# 2_INTERFACES_EXTERNAS.net
KiCad netlist of a schematic drawn in Altium Designer
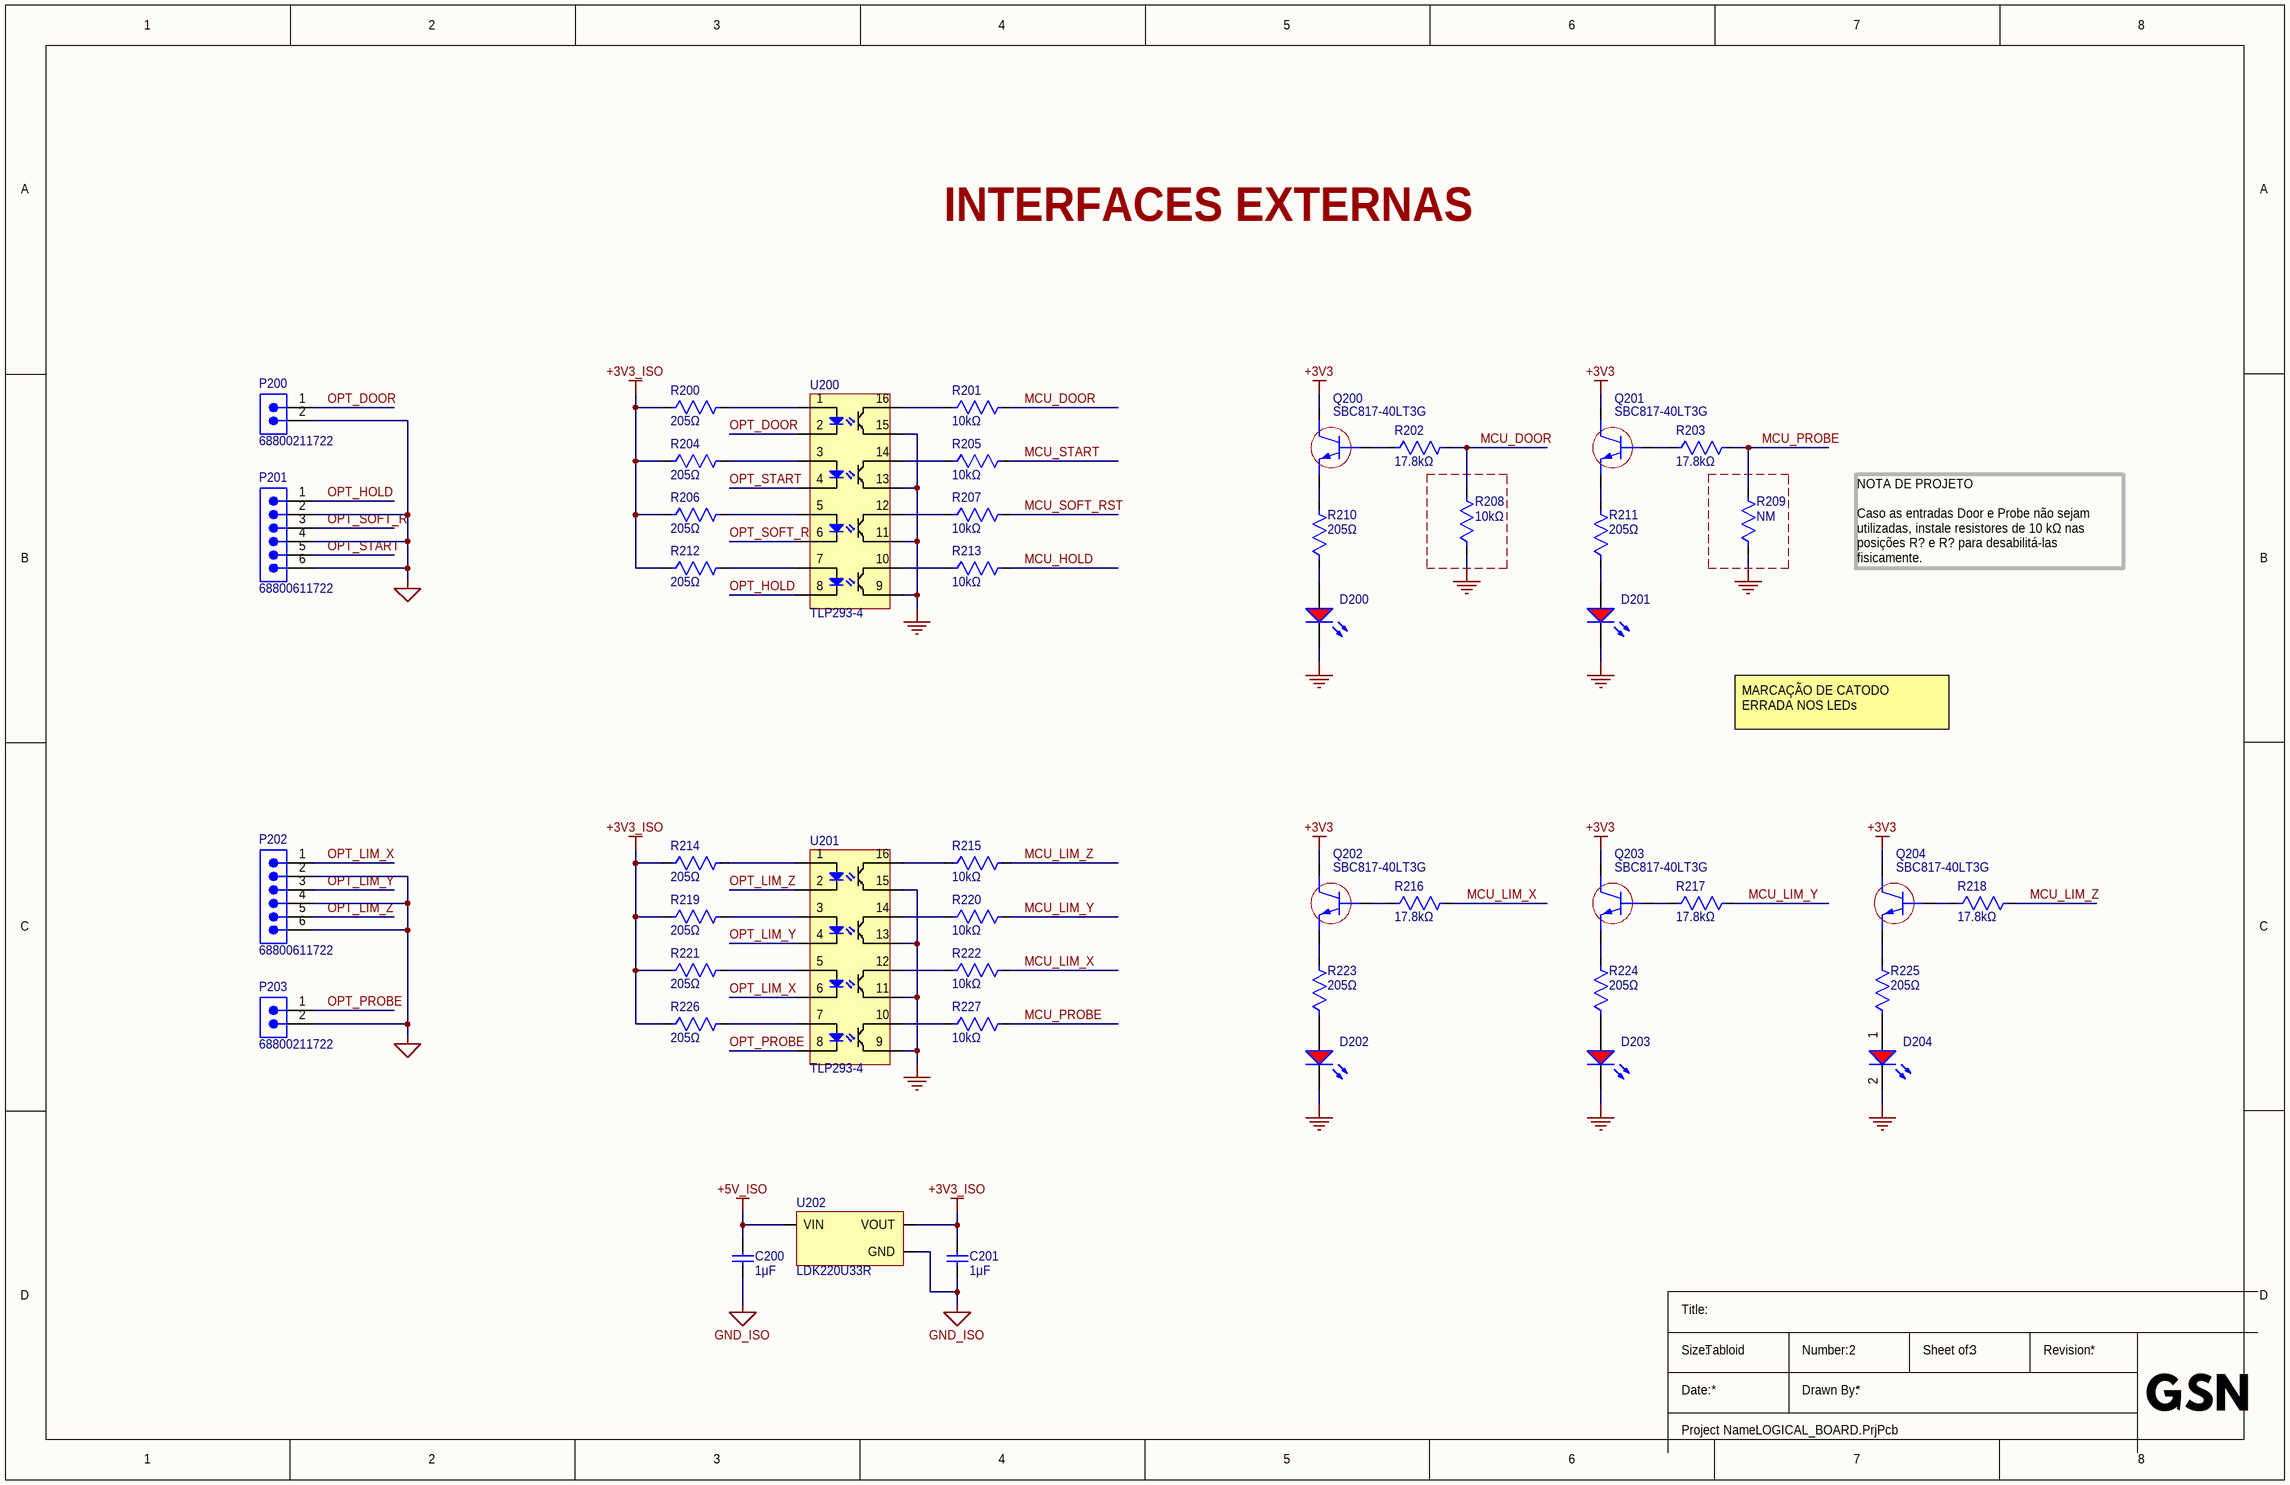
[diagram p0: 2_INTERFACES_EXTERNAS.SchDoc]

(export (version "E")
  (design (tool "Eeschema 10.0.6"))
  (components
    (comp (ref "C200")
      (value "1μF")
      (footprint "WCAP-CSGP_0603_L1.6W0.8H0.8_Wave")
      (description "WCAP-CSGP Multilayer Ceramic Chip Capacitor, General Purpose, size 0603, 1μF, 16V")
      (fields
        (field (name "MANUFACTURER PART NUMBER") "885012206052")
        (field (name "MANUFACTURER") "Wurth Elektronik")
      )
      (libsource (lib "WE - Passive Components") (part "Capacitor_Non-Polarized"))
    )
    (comp (ref "C201")
      (value "1μF")
      (footprint "WCAP-CSGP_0603_L1.6W0.8H0.8_Wave")
      (description "WCAP-CSGP Multilayer Ceramic Chip Capacitor, General Purpose, size 0603, 1μF, 16V")
      (fields
        (field (name "MANUFACTURER PART NUMBER") "885012206052")
        (field (name "MANUFACTURER") "Wurth Elektronik")
      )
      (libsource (lib "WE - Passive Components") (part "Capacitor_Non-Polarized"))
    )
    (comp (ref "D200")
      (value "Red, 2V, 140deg")
      (footprint "WL-SMCW_0603_150060xx75003")
      (description "WL-SMCW Mono-color Chip LED Waterclear, SMT, size 0603, Red, 2V, 140°")
      (fields
        (field (name "MANUFACTURER PART NUMBER") "150060RS75003")
        (field (name "MANUFACTURER") "Wurth Elektronik")
      )
      (libsource (lib "WE - Optoelectronic Components") (part "LED_Red_1A-2K"))
    )
    (comp (ref "D201")
      (value "Red, 2V, 140deg")
      (footprint "WL-SMCW_0603_150060xx75003")
      (description "WL-SMCW Mono-color Chip LED Waterclear, SMT, size 0603, Red, 2V, 140°")
      (fields
        (field (name "MANUFACTURER PART NUMBER") "150060RS75003")
        (field (name "MANUFACTURER") "Wurth Elektronik")
      )
      (libsource (lib "WE - Optoelectronic Components") (part "LED_Red_1A-2K"))
    )
    (comp (ref "D202")
      (value "Red, 2V, 140deg")
      (footprint "WL-SMCW_0603_150060xx75003")
      (description "WL-SMCW Mono-color Chip LED Waterclear, SMT, size 0603, Red, 2V, 140°")
      (fields
        (field (name "MANUFACTURER PART NUMBER") "150060RS75003")
        (field (name "MANUFACTURER") "Wurth Elektronik")
      )
      (libsource (lib "WE - Optoelectronic Components") (part "LED_Red_1A-2K"))
    )
    (comp (ref "D203")
      (value "Red, 2V, 140deg")
      (footprint "WL-SMCW_0603_150060xx75003")
      (description "WL-SMCW Mono-color Chip LED Waterclear, SMT, size 0603, Red, 2V, 140°")
      (fields
        (field (name "MANUFACTURER PART NUMBER") "150060RS75003")
        (field (name "MANUFACTURER") "Wurth Elektronik")
      )
      (libsource (lib "WE - Optoelectronic Components") (part "LED_Red_1A-2K"))
    )
    (comp (ref "D204")
      (value "Red, 2V, 140deg")
      (footprint "WL-SMCW_0603_150060xx75003")
      (description "WL-SMCW Mono-color Chip LED Waterclear, SMT, size 0603, Red, 2V, 140°")
      (fields
        (field (name "MANUFACTURER PART NUMBER") "150060RS75003")
        (field (name "MANUFACTURER") "Wurth Elektronik")
      )
      (libsource (lib "") (part "LED_Red_1A-2K_1"))
    )
    (comp (ref "P200")
      (value "68800211722")
      (footprint "68800211722")
      (description "WR-WTB “J” Type THT Male Horizontal Shrouded Header, pitch 2.5 mm, 2 pins")
      (fields (field (name "MANUFACTURER") "Wurth Elektronik"))
      (libsource (lib "WE - Electromechanical Components") (part "Header_Male_1R_02P"))
    )
    (comp (ref "P201")
      (value "68800611722")
      (footprint "68800611722")
      (description "WR-WTB “J” Type THT Male Horizontal Shrouded Header, pitch 2.5 mm, 6 pins")
      (fields (field (name "MANUFACTURER") "Wurth Elektronik"))
      (libsource (lib "WE - Electromechanical Components") (part "Header_Male_1R_06P"))
    )
    (comp (ref "P202")
      (value "68800611722")
      (footprint "68800611722")
      (description "WR-WTB “J” Type THT Male Horizontal Shrouded Header, pitch 2.5 mm, 6 pins")
      (fields (field (name "MANUFACTURER") "Wurth Elektronik"))
      (libsource (lib "WE - Electromechanical Components") (part "Header_Male_1R_06P"))
    )
    (comp (ref "P203")
      (value "68800211722")
      (footprint "68800211722")
      (description "WR-WTB “J” Type THT Male Horizontal Shrouded Header, pitch 2.5 mm, 2 pins")
      (fields (field (name "MANUFACTURER") "Wurth Elektronik"))
      (libsource (lib "WE - Electromechanical Components") (part "Header_Male_1R_02P"))
    )
    (comp (ref "Q200")
      (value "SBC817-40LT3G")
      (footprint "SOT-23-3")
      (description "TRANS NPN 45V 0.5A SOT23-3")
      (fields (field (name "MANUFACTURER") "onsemi"))
      (libsource (lib "Transistors") (part "SBC817-40LT3G"))
    )
    (comp (ref "Q201")
      (value "SBC817-40LT3G")
      (footprint "SOT-23-3")
      (description "TRANS NPN 45V 0.5A SOT23-3")
      (fields (field (name "MANUFACTURER") "onsemi"))
      (libsource (lib "Transistors") (part "SBC817-40LT3G"))
    )
    (comp (ref "Q202")
      (value "SBC817-40LT3G")
      (footprint "SOT-23-3")
      (description "TRANS NPN 45V 0.5A SOT23-3")
      (fields (field (name "MANUFACTURER") "onsemi"))
      (libsource (lib "Transistors") (part "SBC817-40LT3G"))
    )
    (comp (ref "Q203")
      (value "SBC817-40LT3G")
      (footprint "SOT-23-3")
      (description "TRANS NPN 45V 0.5A SOT23-3")
      (fields (field (name "MANUFACTURER") "onsemi"))
      (libsource (lib "Transistors") (part "SBC817-40LT3G"))
    )
    (comp (ref "Q204")
      (value "SBC817-40LT3G")
      (footprint "SOT-23-3")
      (description "TRANS NPN 45V 0.5A SOT23-3")
      (fields (field (name "MANUFACTURER") "onsemi"))
      (libsource (lib "Transistors") (part "SBC817-40LT3G"))
    )
    (comp (ref "R200")
      (value "205Ω")
      (footprint "0603-WAVE")
      (description "RES 205 OHM 1% 1/10W 0603")
      (fields
        (field (name "MANUFACTURER PART NUMBER") "RC0603FR-07205RL")
        (field (name "MANUFACTURER") "Yageo Group")
      )
      (libsource (lib "Resistors-0603-E96-Yageo") (part "RC0603FR-07205RL"))
    )
    (comp (ref "R201")
      (value "10kΩ")
      (footprint "0603-WAVE")
      (description "RES 10K OHM 1% 1/10W 0603")
      (fields
        (field (name "MANUFACTURER PART NUMBER") "RC0603FR-0710KL")
        (field (name "MANUFACTURER") "Yageo Group")
      )
      (libsource (lib "Resistors-0603-E96-Yageo") (part "RC0603FR-0710KL"))
    )
    (comp (ref "R202")
      (value "17.8kΩ")
      (footprint "0603-WAVE")
      (description "RES 17.8K OHM 1% 1/10W 0603")
      (fields
        (field (name "MANUFACTURER PART NUMBER") "RC0603FR-0717K8L")
        (field (name "MANUFACTURER") "Yageo Group")
      )
      (libsource (lib "Resistors-0603-E96-Yageo") (part "RC0603FR-0717K8L"))
    )
    (comp (ref "R203")
      (value "17.8kΩ")
      (footprint "0603-WAVE")
      (description "RES 17.8K OHM 1% 1/10W 0603")
      (fields
        (field (name "MANUFACTURER PART NUMBER") "RC0603FR-0717K8L")
        (field (name "MANUFACTURER") "Yageo Group")
      )
      (libsource (lib "Resistors-0603-E96-Yageo") (part "RC0603FR-0717K8L"))
    )
    (comp (ref "R204")
      (value "205Ω")
      (footprint "0603-WAVE")
      (description "RES 205 OHM 1% 1/10W 0603")
      (fields
        (field (name "MANUFACTURER PART NUMBER") "RC0603FR-07205RL")
        (field (name "MANUFACTURER") "Yageo Group")
      )
      (libsource (lib "Resistors-0603-E96-Yageo") (part "RC0603FR-07205RL"))
    )
    (comp (ref "R205")
      (value "10kΩ")
      (footprint "0603-WAVE")
      (description "RES 10K OHM 1% 1/10W 0603")
      (fields
        (field (name "MANUFACTURER PART NUMBER") "RC0603FR-0710KL")
        (field (name "MANUFACTURER") "Yageo Group")
      )
      (libsource (lib "Resistors-0603-E96-Yageo") (part "RC0603FR-0710KL"))
    )
    (comp (ref "R206")
      (value "205Ω")
      (footprint "0603-WAVE")
      (description "RES 205 OHM 1% 1/10W 0603")
      (fields
        (field (name "MANUFACTURER PART NUMBER") "RC0603FR-07205RL")
        (field (name "MANUFACTURER") "Yageo Group")
      )
      (libsource (lib "Resistors-0603-E96-Yageo") (part "RC0603FR-07205RL"))
    )
    (comp (ref "R207")
      (value "10kΩ")
      (footprint "0603-WAVE")
      (description "RES 10K OHM 1% 1/10W 0603")
      (fields
        (field (name "MANUFACTURER PART NUMBER") "RC0603FR-0710KL")
        (field (name "MANUFACTURER") "Yageo Group")
      )
      (libsource (lib "Resistors-0603-E96-Yageo") (part "RC0603FR-0710KL"))
    )
    (comp (ref "R208")
      (value "10kΩ")
      (footprint "0603-WAVE")
      (description "RES 10K OHM 1% 1/10W 0603")
      (fields
        (field (name "MANUFACTURER PART NUMBER") "RC0603FR-0710KL")
        (field (name "MANUFACTURER") "Yageo Group")
      )
      (libsource (lib "Resistors-0603-E96-Yageo") (part "RC0603FR-0710KL"))
    )
    (comp (ref "R209")
      (value "NM")
      (footprint "0603-WAVE")
      (description "RES 10K OHM 1% 1/10W 0603")
      (fields
        (field (name "MANUFACTURER PART NUMBER") "RC0603FR-0710KL")
        (field (name "MANUFACTURER") "Yageo Group")
      )
      (libsource (lib "Resistors-0603-E96-Yageo") (part "RC0603FR-0710KL"))
    )
    (comp (ref "R210")
      (value "205Ω")
      (footprint "0603-WAVE")
      (description "RES 205 OHM 1% 1/10W 0603")
      (fields
        (field (name "MANUFACTURER PART NUMBER") "RC0603FR-07205RL")
        (field (name "MANUFACTURER") "Yageo Group")
      )
      (libsource (lib "Resistors-0603-E96-Yageo") (part "RC0603FR-07205RL"))
    )
    (comp (ref "R211")
      (value "205Ω")
      (footprint "0603-WAVE")
      (description "RES 205 OHM 1% 1/10W 0603")
      (fields
        (field (name "MANUFACTURER PART NUMBER") "RC0603FR-07205RL")
        (field (name "MANUFACTURER") "Yageo Group")
      )
      (libsource (lib "Resistors-0603-E96-Yageo") (part "RC0603FR-07205RL"))
    )
    (comp (ref "R212")
      (value "205Ω")
      (footprint "0603-WAVE")
      (description "RES 205 OHM 1% 1/10W 0603")
      (fields
        (field (name "MANUFACTURER PART NUMBER") "RC0603FR-07205RL")
        (field (name "MANUFACTURER") "Yageo Group")
      )
      (libsource (lib "Resistors-0603-E96-Yageo") (part "RC0603FR-07205RL"))
    )
    (comp (ref "R213")
      (value "10kΩ")
      (footprint "0603-WAVE")
      (description "RES 10K OHM 1% 1/10W 0603")
      (fields
        (field (name "MANUFACTURER PART NUMBER") "RC0603FR-0710KL")
        (field (name "MANUFACTURER") "Yageo Group")
      )
      (libsource (lib "Resistors-0603-E96-Yageo") (part "RC0603FR-0710KL"))
    )
    (comp (ref "R214")
      (value "205Ω")
      (footprint "0603-WAVE")
      (description "RES 205 OHM 1% 1/10W 0603")
      (fields
        (field (name "MANUFACTURER PART NUMBER") "RC0603FR-07205RL")
        (field (name "MANUFACTURER") "Yageo Group")
      )
      (libsource (lib "Resistors-0603-E96-Yageo") (part "RC0603FR-07205RL"))
    )
    (comp (ref "R215")
      (value "10kΩ")
      (footprint "0603-WAVE")
      (description "RES 10K OHM 1% 1/10W 0603")
      (fields
        (field (name "MANUFACTURER PART NUMBER") "RC0603FR-0710KL")
        (field (name "MANUFACTURER") "Yageo Group")
      )
      (libsource (lib "Resistors-0603-E96-Yageo") (part "RC0603FR-0710KL"))
    )
    (comp (ref "R216")
      (value "17.8kΩ")
      (footprint "0603-WAVE")
      (description "RES 17.8K OHM 1% 1/10W 0603")
      (fields
        (field (name "MANUFACTURER PART NUMBER") "RC0603FR-0717K8L")
        (field (name "MANUFACTURER") "Yageo Group")
      )
      (libsource (lib "Resistors-0603-E96-Yageo") (part "RC0603FR-0717K8L"))
    )
    (comp (ref "R217")
      (value "17.8kΩ")
      (footprint "0603-WAVE")
      (description "RES 17.8K OHM 1% 1/10W 0603")
      (fields
        (field (name "MANUFACTURER PART NUMBER") "RC0603FR-0717K8L")
        (field (name "MANUFACTURER") "Yageo Group")
      )
      (libsource (lib "Resistors-0603-E96-Yageo") (part "RC0603FR-0717K8L"))
    )
    (comp (ref "R218")
      (value "17.8kΩ")
      (footprint "0603-WAVE")
      (description "RES 17.8K OHM 1% 1/10W 0603")
      (fields
        (field (name "MANUFACTURER PART NUMBER") "RC0603FR-0717K8L")
        (field (name "MANUFACTURER") "Yageo Group")
      )
      (libsource (lib "Resistors-0603-E96-Yageo") (part "RC0603FR-0717K8L"))
    )
    (comp (ref "R219")
      (value "205Ω")
      (footprint "0603-WAVE")
      (description "RES 205 OHM 1% 1/10W 0603")
      (fields
        (field (name "MANUFACTURER PART NUMBER") "RC0603FR-07205RL")
        (field (name "MANUFACTURER") "Yageo Group")
      )
      (libsource (lib "Resistors-0603-E96-Yageo") (part "RC0603FR-07205RL"))
    )
    (comp (ref "R220")
      (value "10kΩ")
      (footprint "0603-WAVE")
      (description "RES 10K OHM 1% 1/10W 0603")
      (fields
        (field (name "MANUFACTURER PART NUMBER") "RC0603FR-0710KL")
        (field (name "MANUFACTURER") "Yageo Group")
      )
      (libsource (lib "Resistors-0603-E96-Yageo") (part "RC0603FR-0710KL"))
    )
    (comp (ref "R221")
      (value "205Ω")
      (footprint "0603-WAVE")
      (description "RES 205 OHM 1% 1/10W 0603")
      (fields
        (field (name "MANUFACTURER PART NUMBER") "RC0603FR-07205RL")
        (field (name "MANUFACTURER") "Yageo Group")
      )
      (libsource (lib "Resistors-0603-E96-Yageo") (part "RC0603FR-07205RL"))
    )
    (comp (ref "R222")
      (value "10kΩ")
      (footprint "0603-WAVE")
      (description "RES 10K OHM 1% 1/10W 0603")
      (fields
        (field (name "MANUFACTURER PART NUMBER") "RC0603FR-0710KL")
        (field (name "MANUFACTURER") "Yageo Group")
      )
      (libsource (lib "Resistors-0603-E96-Yageo") (part "RC0603FR-0710KL"))
    )
    (comp (ref "R223")
      (value "205Ω")
      (footprint "0603-WAVE")
      (description "RES 205 OHM 1% 1/10W 0603")
      (fields
        (field (name "MANUFACTURER PART NUMBER") "RC0603FR-07205RL")
        (field (name "MANUFACTURER") "Yageo Group")
      )
      (libsource (lib "Resistors-0603-E96-Yageo") (part "RC0603FR-07205RL"))
    )
    (comp (ref "R224")
      (value "205Ω")
      (footprint "0603-WAVE")
      (description "RES 205 OHM 1% 1/10W 0603")
      (fields
        (field (name "MANUFACTURER PART NUMBER") "RC0603FR-07205RL")
        (field (name "MANUFACTURER") "Yageo Group")
      )
      (libsource (lib "Resistors-0603-E96-Yageo") (part "RC0603FR-07205RL"))
    )
    (comp (ref "R225")
      (value "205Ω")
      (footprint "0603-WAVE")
      (description "RES 205 OHM 1% 1/10W 0603")
      (fields
        (field (name "MANUFACTURER PART NUMBER") "RC0603FR-07205RL")
        (field (name "MANUFACTURER") "Yageo Group")
      )
      (libsource (lib "Resistors-0603-E96-Yageo") (part "RC0603FR-07205RL"))
    )
    (comp (ref "R226")
      (value "205Ω")
      (footprint "0603-WAVE")
      (description "RES 205 OHM 1% 1/10W 0603")
      (fields
        (field (name "MANUFACTURER PART NUMBER") "RC0603FR-07205RL")
        (field (name "MANUFACTURER") "Yageo Group")
      )
      (libsource (lib "Resistors-0603-E96-Yageo") (part "RC0603FR-07205RL"))
    )
    (comp (ref "R227")
      (value "10kΩ")
      (footprint "0603-WAVE")
      (description "RES 10K OHM 1% 1/10W 0603")
      (fields
        (field (name "MANUFACTURER PART NUMBER") "RC0603FR-0710KL")
        (field (name "MANUFACTURER") "Yageo Group")
      )
      (libsource (lib "Resistors-0603-E96-Yageo") (part "RC0603FR-0710KL"))
    )
    (comp (ref "U200")
      (value "TLP293-4")
      (footprint "SO-16")
      (description "OPTOISO 3.75KV 4CH TRANS 16-SO")
      (fields
        (field (name "MANUFACTURER") "Toshiba")
        (field (name "MANUFACTURER PART NUMBER") "TLP293-4(TP,E")
      )
      (libsource (lib "Optocouplers") (part "TLP293-4"))
    )
    (comp (ref "U201")
      (value "TLP293-4")
      (footprint "SO-16")
      (description "OPTOISO 3.75KV 4CH TRANS 16-SO")
      (fields
        (field (name "MANUFACTURER") "Toshiba")
        (field (name "MANUFACTURER PART NUMBER") "TLP293-4(TP,E")
      )
      (libsource (lib "Optocouplers") (part "TLP293-4"))
    )
    (comp (ref "U202")
      (value "LDK220U33R")
      (footprint "SOT-89")
      (description "IC REG LINEAR 3.3V 200MA SOT89")
      (fields (field (name "MANUFACTURER") "STMicroelectronics"))
      (libsource (lib "Voltage-Regulators") (part "LDK220U33R"))
    )
  )
  (nets
    (net (code "1") (name "+3V3") (class "Default")
      (node (ref "Q200") (pin "3") (pinfunction "C_3") (pintype "passive"))
      (node (ref "Q201") (pin "3") (pinfunction "C_3") (pintype "passive"))
      (node (ref "Q202") (pin "3") (pinfunction "C_3") (pintype "passive"))
      (node (ref "Q203") (pin "3") (pinfunction "C_3") (pintype "passive"))
      (node (ref "Q204") (pin "3") (pinfunction "C_3") (pintype "passive"))
    )
    (net (code "2") (name "+3V3_ISO") (class "Default")
      (node (ref "C201") (pin "2") (pinfunction "2_2") (pintype "passive"))
      (node (ref "R200") (pin "1") (pinfunction "1_1") (pintype "passive"))
      (node (ref "R204") (pin "1") (pinfunction "1_1") (pintype "passive"))
      (node (ref "R206") (pin "1") (pinfunction "1_1") (pintype "passive"))
      (node (ref "R212") (pin "1") (pinfunction "1_1") (pintype "passive"))
      (node (ref "R214") (pin "1") (pinfunction "1_1") (pintype "passive"))
      (node (ref "R219") (pin "1") (pinfunction "1_1") (pintype "passive"))
      (node (ref "R221") (pin "1") (pinfunction "1_1") (pintype "passive"))
      (node (ref "R226") (pin "1") (pinfunction "1_1") (pintype "passive"))
      (node (ref "U202") (pin "1") (pinfunction "VOUT_1") (pintype "passive"))
    )
    (net (code "3") (name "+5V_ISO") (class "Default")
      (node (ref "C200") (pin "2") (pinfunction "2_2") (pintype "passive"))
      (node (ref "U202") (pin "3") (pinfunction "VIN_3") (pintype "passive"))
    )
    (net (code "4") (name "/MCU_DOOR") (class "Default")
      (node (ref "R201") (pin "2") (pinfunction "2_2") (pintype "passive"))
      (node (ref "R202") (pin "2") (pinfunction "2_2") (pintype "passive"))
      (node (ref "R208") (pin "2") (pinfunction "2_2") (pintype "passive"))
    )
    (net (code "5") (name "/MCU_HOLD") (class "Default")
      (node (ref "R213") (pin "2") (pinfunction "2_2") (pintype "passive"))
    )
    (net (code "6") (name "/MCU_LIM_X") (class "Default")
      (node (ref "R216") (pin "2") (pinfunction "2_2") (pintype "passive"))
      (node (ref "R222") (pin "2") (pinfunction "2_2") (pintype "passive"))
    )
    (net (code "7") (name "/MCU_LIM_Y") (class "Default")
      (node (ref "R217") (pin "2") (pinfunction "2_2") (pintype "passive"))
      (node (ref "R220") (pin "2") (pinfunction "2_2") (pintype "passive"))
    )
    (net (code "8") (name "/MCU_LIM_Z") (class "Default")
      (node (ref "R215") (pin "2") (pinfunction "2_2") (pintype "passive"))
      (node (ref "R218") (pin "2") (pinfunction "2_2") (pintype "passive"))
    )
    (net (code "9") (name "/MCU_PROBE") (class "Default")
      (node (ref "R203") (pin "2") (pinfunction "2_2") (pintype "passive"))
      (node (ref "R209") (pin "2") (pinfunction "2_2") (pintype "passive"))
      (node (ref "R227") (pin "2") (pinfunction "2_2") (pintype "passive"))
    )
    (net (code "10") (name "/MCU_SOFT_RST") (class "Default")
      (node (ref "R207") (pin "2") (pinfunction "2_2") (pintype "passive"))
    )
    (net (code "11") (name "/MCU_START") (class "Default")
      (node (ref "R205") (pin "2") (pinfunction "2_2") (pintype "passive"))
    )
    (net (code "12") (name "/OPT_DOOR") (class "Default")
      (node (ref "P200") (pin "1") (pinfunction "1_1") (pintype "passive"))
      (node (ref "U200") (pin "2") (pinfunction "2_2") (pintype "passive"))
    )
    (net (code "13") (name "/OPT_HOLD") (class "Default")
      (node (ref "P201") (pin "1") (pinfunction "1_1") (pintype "passive"))
      (node (ref "U200") (pin "8") (pinfunction "8_8") (pintype "passive"))
    )
    (net (code "14") (name "/OPT_LIM_X") (class "Default")
      (node (ref "P202") (pin "1") (pinfunction "1_1") (pintype "passive"))
      (node (ref "U201") (pin "6") (pinfunction "6_6") (pintype "passive"))
    )
    (net (code "15") (name "/OPT_LIM_Y") (class "Default")
      (node (ref "P202") (pin "3") (pinfunction "3_3") (pintype "passive"))
      (node (ref "U201") (pin "4") (pinfunction "4_4") (pintype "passive"))
    )
    (net (code "16") (name "/OPT_LIM_Z") (class "Default")
      (node (ref "P202") (pin "5") (pinfunction "5_5") (pintype "passive"))
      (node (ref "U201") (pin "2") (pinfunction "2_2") (pintype "passive"))
    )
    (net (code "17") (name "/OPT_PROBE") (class "Default")
      (node (ref "P203") (pin "1") (pinfunction "1_1") (pintype "passive"))
      (node (ref "U201") (pin "8") (pinfunction "8_8") (pintype "passive"))
    )
    (net (code "18") (name "/OPT_SOFT_R") (class "Default")
      (node (ref "P201") (pin "3") (pinfunction "3_3") (pintype "passive"))
      (node (ref "U200") (pin "6") (pinfunction "6_6") (pintype "passive"))
    )
    (net (code "19") (name "/OPT_START") (class "Default")
      (node (ref "P201") (pin "5") (pinfunction "5_5") (pintype "passive"))
      (node (ref "U200") (pin "4") (pinfunction "4_4") (pintype "passive"))
    )
    (net (code "20") (name "GND") (class "Default")
      (node (ref "D200") (pin "2") (pinfunction "K_2") (pintype "passive"))
      (node (ref "D201") (pin "2") (pinfunction "K_2") (pintype "passive"))
      (node (ref "D202") (pin "2") (pinfunction "K_2") (pintype "passive"))
      (node (ref "D203") (pin "2") (pinfunction "K_2") (pintype "passive"))
      (node (ref "D204") (pin "2") (pinfunction "K_2") (pintype "passive"))
      (node (ref "R208") (pin "1") (pinfunction "1_1") (pintype "passive"))
      (node (ref "R209") (pin "1") (pinfunction "1_1") (pintype "passive"))
      (node (ref "U200") (pin "11") (pinfunction "11_11") (pintype "passive"))
      (node (ref "U200") (pin "13") (pinfunction "13_13") (pintype "passive"))
      (node (ref "U200") (pin "15") (pinfunction "15_15") (pintype "passive"))
      (node (ref "U200") (pin "9") (pinfunction "9_9") (pintype "passive"))
      (node (ref "U201") (pin "11") (pinfunction "11_11") (pintype "passive"))
      (node (ref "U201") (pin "13") (pinfunction "13_13") (pintype "passive"))
      (node (ref "U201") (pin "15") (pinfunction "15_15") (pintype "passive"))
      (node (ref "U201") (pin "9") (pinfunction "9_9") (pintype "passive"))
    )
    (net (code "21") (name "GND_ISO") (class "Default")
      (node (ref "C200") (pin "1") (pinfunction "1_1") (pintype "passive"))
      (node (ref "C201") (pin "1") (pinfunction "1_1") (pintype "passive"))
      (node (ref "P200") (pin "2") (pinfunction "2_2") (pintype "passive"))
      (node (ref "P201") (pin "2") (pinfunction "2_2") (pintype "passive"))
      (node (ref "P201") (pin "4") (pinfunction "4_4") (pintype "passive"))
      (node (ref "P201") (pin "6") (pinfunction "6_6") (pintype "passive"))
      (node (ref "P202") (pin "2") (pinfunction "2_2") (pintype "passive"))
      (node (ref "P202") (pin "4") (pinfunction "4_4") (pintype "passive"))
      (node (ref "P202") (pin "6") (pinfunction "6_6") (pintype "passive"))
      (node (ref "P203") (pin "2") (pinfunction "2_2") (pintype "passive"))
      (node (ref "U202") (pin "2") (pinfunction "GND_2") (pintype "passive"))
    )
    (net (code "22") (name "Net-(D200-A)") (class "Default")
      (node (ref "D200") (pin "1") (pinfunction "A_1") (pintype "passive"))
      (node (ref "R210") (pin "1") (pinfunction "1_1") (pintype "passive"))
    )
    (net (code "23") (name "Net-(D201-A)") (class "Default")
      (node (ref "D201") (pin "1") (pinfunction "A_1") (pintype "passive"))
      (node (ref "R211") (pin "1") (pinfunction "1_1") (pintype "passive"))
    )
    (net (code "24") (name "Net-(D202-A)") (class "Default")
      (node (ref "D202") (pin "1") (pinfunction "A_1") (pintype "passive"))
      (node (ref "R223") (pin "1") (pinfunction "1_1") (pintype "passive"))
    )
    (net (code "25") (name "Net-(D203-A)") (class "Default")
      (node (ref "D203") (pin "1") (pinfunction "A_1") (pintype "passive"))
      (node (ref "R224") (pin "1") (pinfunction "1_1") (pintype "passive"))
    )
    (net (code "26") (name "Net-(D204-A)") (class "Default")
      (node (ref "D204") (pin "1") (pinfunction "A_1") (pintype "passive"))
      (node (ref "R225") (pin "1") (pinfunction "1_1") (pintype "passive"))
    )
    (net (code "27") (name "Net-(Q200-B)") (class "Default")
      (node (ref "Q200") (pin "1") (pinfunction "B_1") (pintype "passive"))
      (node (ref "R202") (pin "1") (pinfunction "1_1") (pintype "passive"))
    )
    (net (code "28") (name "Net-(Q200-E)") (class "Default")
      (node (ref "Q200") (pin "2") (pinfunction "E_2") (pintype "passive"))
      (node (ref "R210") (pin "2") (pinfunction "2_2") (pintype "passive"))
    )
    (net (code "29") (name "Net-(Q201-B)") (class "Default")
      (node (ref "Q201") (pin "1") (pinfunction "B_1") (pintype "passive"))
      (node (ref "R203") (pin "1") (pinfunction "1_1") (pintype "passive"))
    )
    (net (code "30") (name "Net-(Q201-E)") (class "Default")
      (node (ref "Q201") (pin "2") (pinfunction "E_2") (pintype "passive"))
      (node (ref "R211") (pin "2") (pinfunction "2_2") (pintype "passive"))
    )
    (net (code "31") (name "Net-(Q202-B)") (class "Default")
      (node (ref "Q202") (pin "1") (pinfunction "B_1") (pintype "passive"))
      (node (ref "R216") (pin "1") (pinfunction "1_1") (pintype "passive"))
    )
    (net (code "32") (name "Net-(Q202-E)") (class "Default")
      (node (ref "Q202") (pin "2") (pinfunction "E_2") (pintype "passive"))
      (node (ref "R223") (pin "2") (pinfunction "2_2") (pintype "passive"))
    )
    (net (code "33") (name "Net-(Q203-B)") (class "Default")
      (node (ref "Q203") (pin "1") (pinfunction "B_1") (pintype "passive"))
      (node (ref "R217") (pin "1") (pinfunction "1_1") (pintype "passive"))
    )
    (net (code "34") (name "Net-(Q203-E)") (class "Default")
      (node (ref "Q203") (pin "2") (pinfunction "E_2") (pintype "passive"))
      (node (ref "R224") (pin "2") (pinfunction "2_2") (pintype "passive"))
    )
    (net (code "35") (name "Net-(Q204-B)") (class "Default")
      (node (ref "Q204") (pin "1") (pinfunction "B_1") (pintype "passive"))
      (node (ref "R218") (pin "1") (pinfunction "1_1") (pintype "passive"))
    )
    (net (code "36") (name "Net-(Q204-E)") (class "Default")
      (node (ref "Q204") (pin "2") (pinfunction "E_2") (pintype "passive"))
      (node (ref "R225") (pin "2") (pinfunction "2_2") (pintype "passive"))
    )
    (net (code "37") (name "Net-(R200-Pad2)") (class "Default")
      (node (ref "R200") (pin "2") (pinfunction "2_2") (pintype "passive"))
      (node (ref "U200") (pin "1") (pinfunction "1_1") (pintype "passive"))
    )
    (net (code "38") (name "Net-(R201-Pad1)") (class "Default")
      (node (ref "R201") (pin "1") (pinfunction "1_1") (pintype "passive"))
      (node (ref "U200") (pin "16") (pinfunction "16_16") (pintype "passive"))
    )
    (net (code "39") (name "Net-(R204-Pad2)") (class "Default")
      (node (ref "R204") (pin "2") (pinfunction "2_2") (pintype "passive"))
      (node (ref "U200") (pin "3") (pinfunction "3_3") (pintype "passive"))
    )
    (net (code "40") (name "Net-(R205-Pad1)") (class "Default")
      (node (ref "R205") (pin "1") (pinfunction "1_1") (pintype "passive"))
      (node (ref "U200") (pin "14") (pinfunction "14_14") (pintype "passive"))
    )
    (net (code "41") (name "Net-(R206-Pad2)") (class "Default")
      (node (ref "R206") (pin "2") (pinfunction "2_2") (pintype "passive"))
      (node (ref "U200") (pin "5") (pinfunction "5_5") (pintype "passive"))
    )
    (net (code "42") (name "Net-(R207-Pad1)") (class "Default")
      (node (ref "R207") (pin "1") (pinfunction "1_1") (pintype "passive"))
      (node (ref "U200") (pin "12") (pinfunction "12_12") (pintype "passive"))
    )
    (net (code "43") (name "Net-(R212-Pad2)") (class "Default")
      (node (ref "R212") (pin "2") (pinfunction "2_2") (pintype "passive"))
      (node (ref "U200") (pin "7") (pinfunction "7_7") (pintype "passive"))
    )
    (net (code "44") (name "Net-(R213-Pad1)") (class "Default")
      (node (ref "R213") (pin "1") (pinfunction "1_1") (pintype "passive"))
      (node (ref "U200") (pin "10") (pinfunction "10_10") (pintype "passive"))
    )
    (net (code "45") (name "Net-(R214-Pad2)") (class "Default")
      (node (ref "R214") (pin "2") (pinfunction "2_2") (pintype "passive"))
      (node (ref "U201") (pin "1") (pinfunction "1_1") (pintype "passive"))
    )
    (net (code "46") (name "Net-(R215-Pad1)") (class "Default")
      (node (ref "R215") (pin "1") (pinfunction "1_1") (pintype "passive"))
      (node (ref "U201") (pin "16") (pinfunction "16_16") (pintype "passive"))
    )
    (net (code "47") (name "Net-(R219-Pad2)") (class "Default")
      (node (ref "R219") (pin "2") (pinfunction "2_2") (pintype "passive"))
      (node (ref "U201") (pin "3") (pinfunction "3_3") (pintype "passive"))
    )
    (net (code "48") (name "Net-(R220-Pad1)") (class "Default")
      (node (ref "R220") (pin "1") (pinfunction "1_1") (pintype "passive"))
      (node (ref "U201") (pin "14") (pinfunction "14_14") (pintype "passive"))
    )
    (net (code "49") (name "Net-(R221-Pad2)") (class "Default")
      (node (ref "R221") (pin "2") (pinfunction "2_2") (pintype "passive"))
      (node (ref "U201") (pin "5") (pinfunction "5_5") (pintype "passive"))
    )
    (net (code "50") (name "Net-(R222-Pad1)") (class "Default")
      (node (ref "R222") (pin "1") (pinfunction "1_1") (pintype "passive"))
      (node (ref "U201") (pin "12") (pinfunction "12_12") (pintype "passive"))
    )
    (net (code "51") (name "Net-(R226-Pad2)") (class "Default")
      (node (ref "R226") (pin "2") (pinfunction "2_2") (pintype "passive"))
      (node (ref "U201") (pin "7") (pinfunction "7_7") (pintype "passive"))
    )
    (net (code "52") (name "Net-(R227-Pad1)") (class "Default")
      (node (ref "R227") (pin "1") (pinfunction "1_1") (pintype "passive"))
      (node (ref "U201") (pin "10") (pinfunction "10_10") (pintype "passive"))
    )
  )
)
